# LPEM.net
KiCad netlist of a schematic drawn in EAGLE
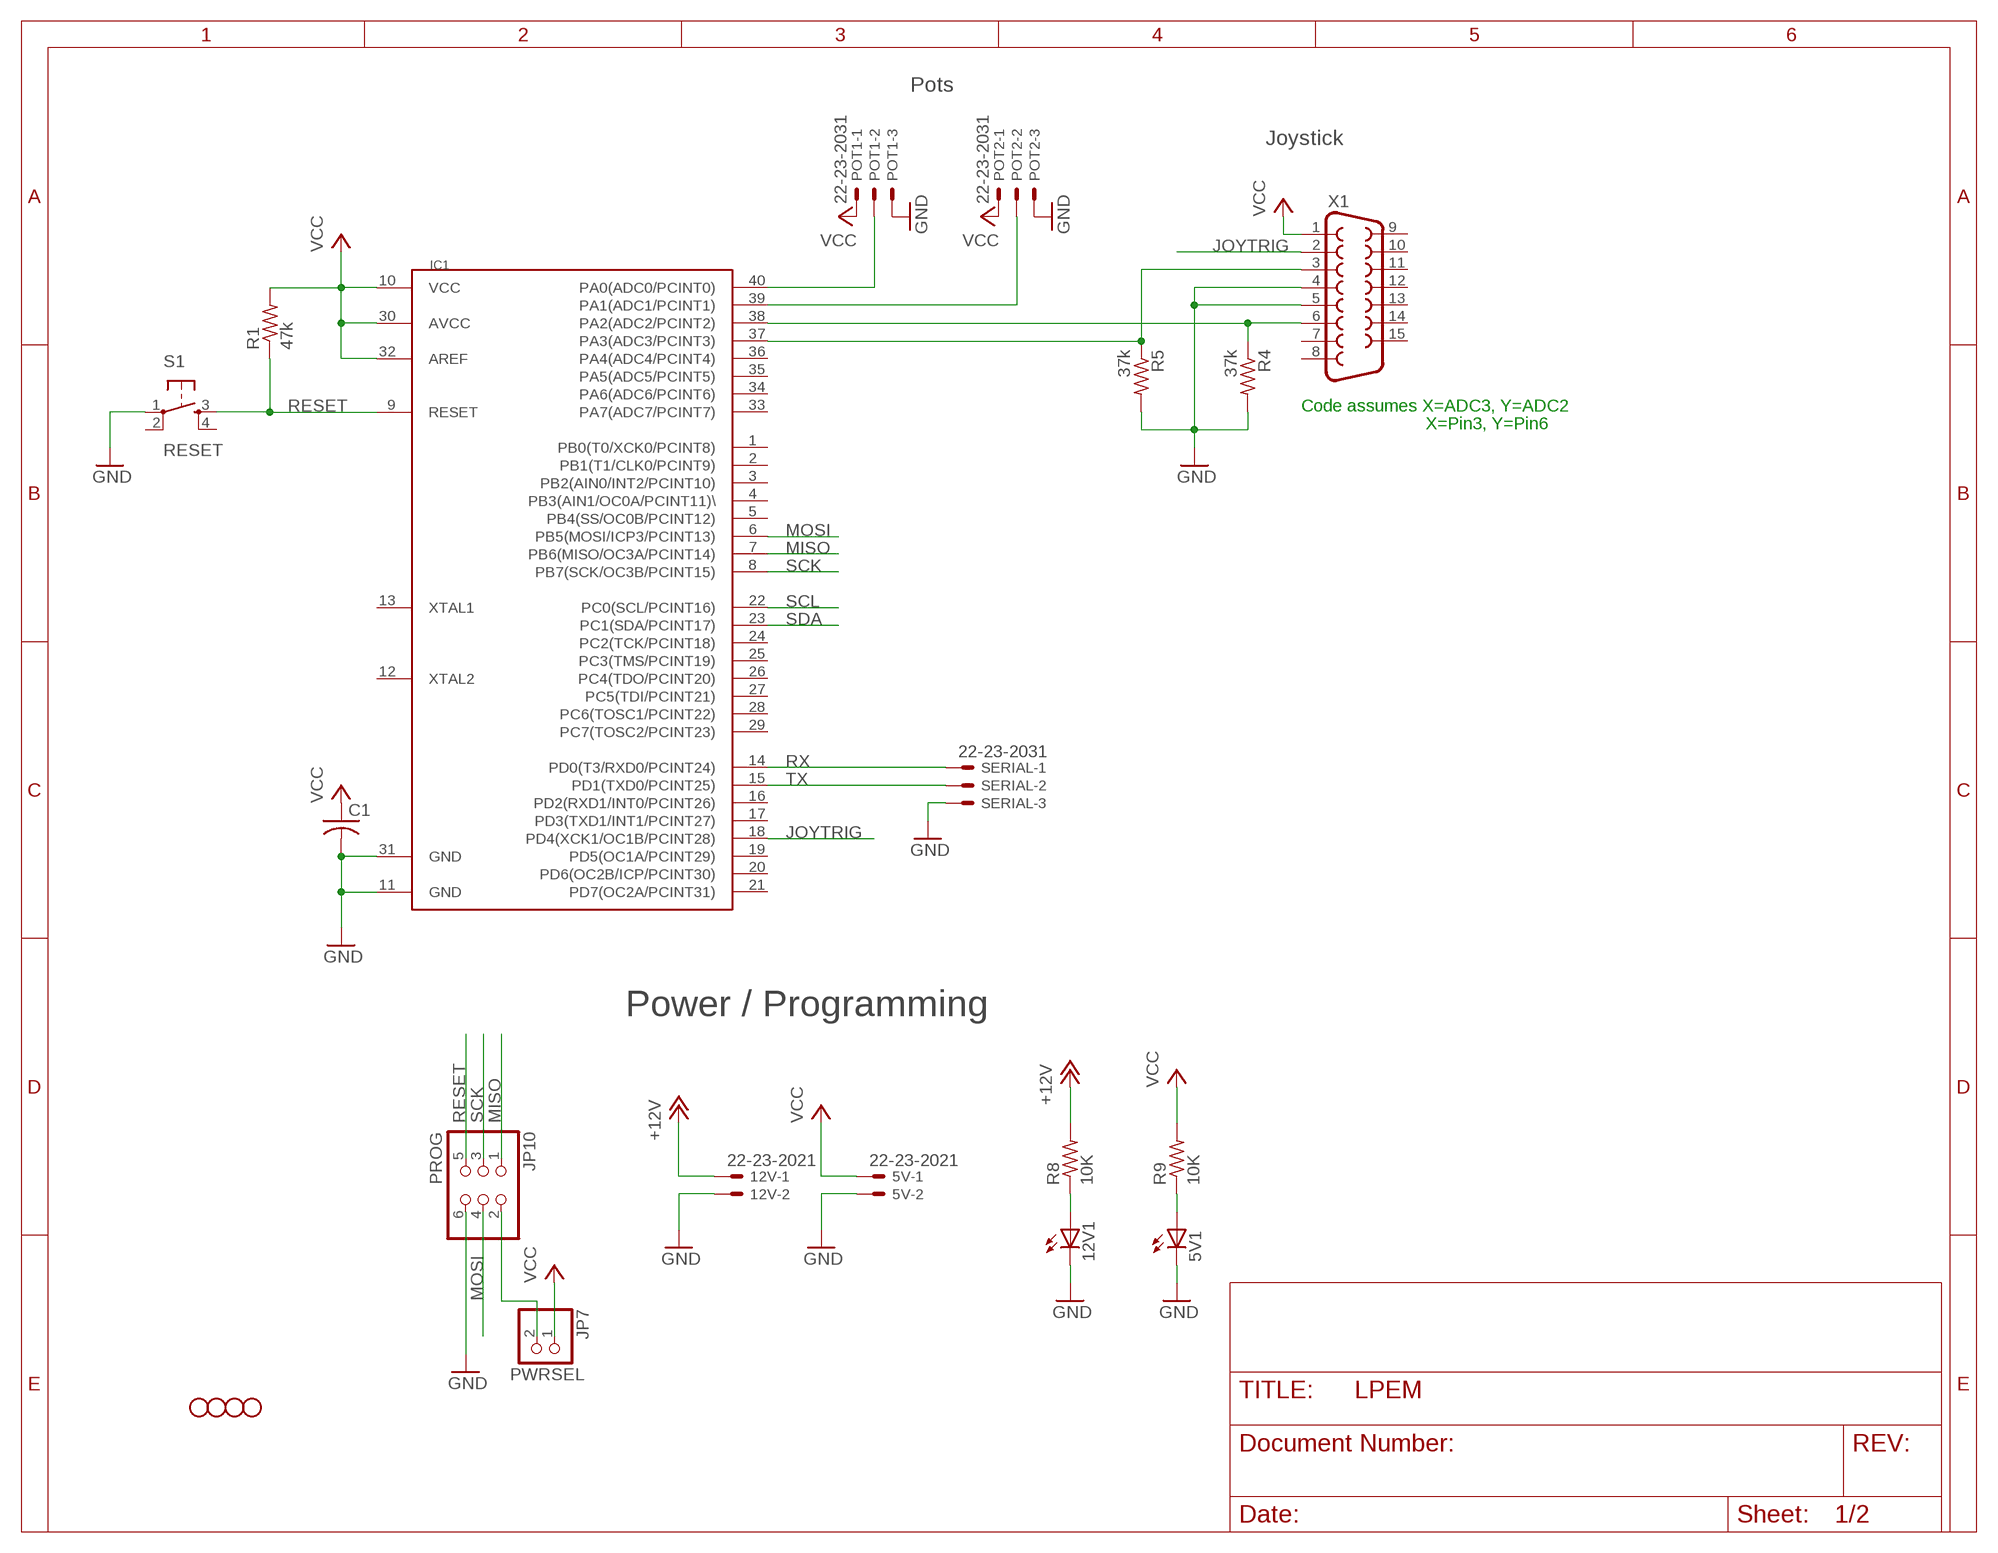
[diagram p0: schematic, sheet 1]
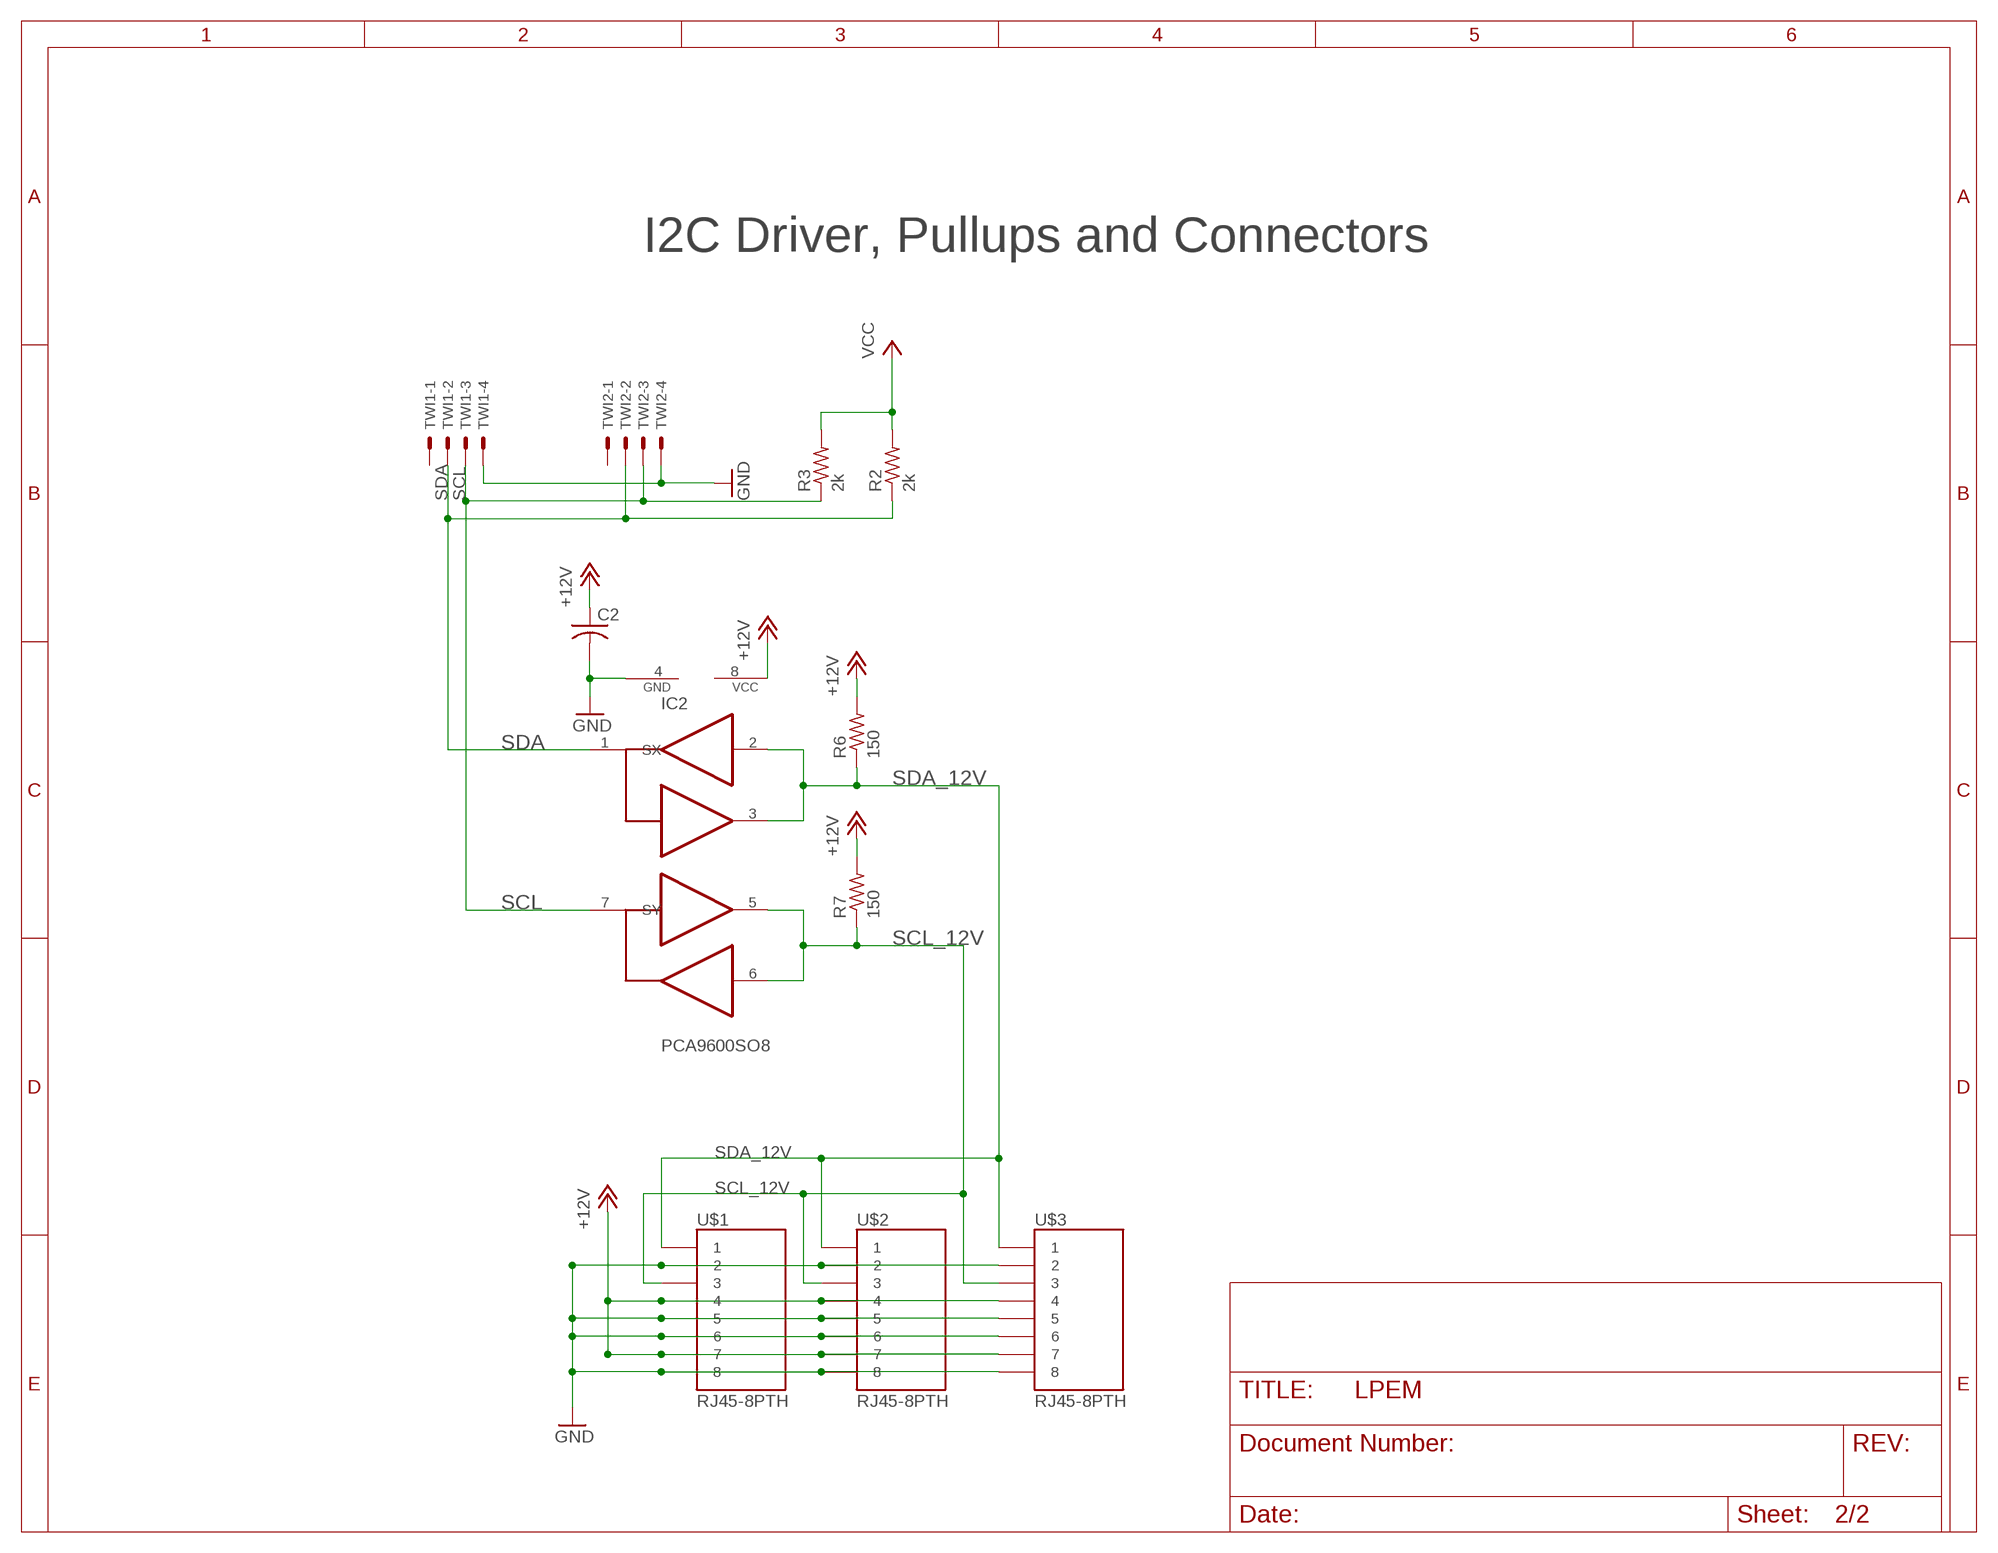
[diagram p1: schematic, sheet 2]

(export (version "E")
  (design (tool "Eeschema 10.0.6"))
  (components
    (comp (ref "5V")
      (value "22-23-2021")
      (footprint "eagle-import:22-23-2021")
      (libsource (lib "eagle-import") (part "22-23-2021"))
    )
    (comp (ref "5V1")
      (value "LED3MM")
      (footprint "eagle-import:LED3MM")
      (libsource (lib "eagle-import") (part "LED3MM"))
    )
    (comp (ref "12V")
      (value "22-23-2021")
      (footprint "eagle-import:22-23-2021")
      (libsource (lib "eagle-import") (part "22-23-2021"))
    )
    (comp (ref "12V1")
      (value "LED3MM")
      (footprint "eagle-import:LED3MM")
      (libsource (lib "eagle-import") (part "LED3MM"))
    )
    (comp (ref "C1")
      (value "C-US025-025X050")
      (footprint "eagle-import:C025-025X050")
      (libsource (lib "eagle-import") (part "C-US025-025X050"))
    )
    (comp (ref "IC1")
      (value "MEGA1284P")
      (footprint "eagle-import:DIL40")
      (libsource (lib "eagle-import") (part "MEGA1284P"))
    )
    (comp (ref "JP1")
      (value "STAND-OFF")
      (footprint "eagle-import:STAND-OFF")
      (libsource (lib "eagle-import") (part "STAND-OFF"))
    )
    (comp (ref "JP2")
      (value "STAND-OFF")
      (footprint "eagle-import:STAND-OFF")
      (libsource (lib "eagle-import") (part "STAND-OFF"))
    )
    (comp (ref "JP7")
      (value "PWRSEL")
      (footprint "eagle-import:1X02")
      (libsource (lib "eagle-import") (part "PINHD-1X2"))
    )
    (comp (ref "JP8")
      (value "STAND-OFF")
      (footprint "eagle-import:STAND-OFF")
      (libsource (lib "eagle-import") (part "STAND-OFF"))
    )
    (comp (ref "JP9")
      (value "STAND-OFF")
      (footprint "eagle-import:STAND-OFF")
      (libsource (lib "eagle-import") (part "STAND-OFF"))
    )
    (comp (ref "JP10")
      (value "PROG")
      (footprint "eagle-import:2X03")
      (libsource (lib "eagle-import") (part "PINHD-2X3"))
    )
    (comp (ref "POT1")
      (value "22-23-2031")
      (footprint "eagle-import:22-23-2031")
      (libsource (lib "eagle-import") (part "22-23-2031"))
    )
    (comp (ref "POT2")
      (value "22-23-2031")
      (footprint "eagle-import:22-23-2031")
      (libsource (lib "eagle-import") (part "22-23-2031"))
    )
    (comp (ref "R1")
      (value "47k")
      (footprint "eagle-import:0204_5")
      (libsource (lib "eagle-import") (part "R-US_0204/5"))
    )
    (comp (ref "R4")
      (value "37k")
      (footprint "eagle-import:0204_5")
      (libsource (lib "eagle-import") (part "R-US_0204/5"))
    )
    (comp (ref "R5")
      (value "37k")
      (footprint "eagle-import:0204_5")
      (libsource (lib "eagle-import") (part "R-US_0204/5"))
    )
    (comp (ref "R8")
      (value "10K")
      (footprint "eagle-import:0204_5")
      (libsource (lib "eagle-import") (part "R-US_0204/5"))
    )
    (comp (ref "R9")
      (value "10K")
      (footprint "eagle-import:0204_5")
      (libsource (lib "eagle-import") (part "R-US_0204/5"))
    )
    (comp (ref "S1")
      (value "RESET")
      (footprint "eagle-import:TACTILE-PTH")
      (libsource (lib "eagle-import") (part "TAC_SWITCHPTH"))
    )
    (comp (ref "SERIAL")
      (value "22-23-2031")
      (footprint "eagle-import:22-23-2031")
      (libsource (lib "eagle-import") (part "22-23-2031"))
    )
    (comp (ref "X1")
      (value "F15HP")
      (footprint "eagle-import:F15HP")
      (libsource (lib "eagle-import") (part "F15HP"))
    )
    (comp (ref "C2")
      (value "C-US025-025X050")
      (footprint "eagle-import:C025-025X050")
      (libsource (lib "eagle-import") (part "C-US025-025X050"))
    )
    (comp (ref "IC2")
      (value "PCA9600SO8")
      (footprint "eagle-import:SO08")
      (libsource (lib "eagle-import") (part "PCA9600SO8"))
    )
    (comp (ref "R2")
      (value "2k")
      (footprint "eagle-import:0204_5")
      (libsource (lib "eagle-import") (part "R-US_0204/5"))
    )
    (comp (ref "R3")
      (value "2k")
      (footprint "eagle-import:0204_5")
      (libsource (lib "eagle-import") (part "R-US_0204/5"))
    )
    (comp (ref "R6")
      (value "150")
      (footprint "eagle-import:0204_5")
      (libsource (lib "eagle-import") (part "R-US_0204/5"))
    )
    (comp (ref "R7")
      (value "150")
      (footprint "eagle-import:0204_5")
      (libsource (lib "eagle-import") (part "R-US_0204/5"))
    )
    (comp (ref "TWI1")
      (value "22-23-2041")
      (footprint "eagle-import:22-23-2041")
      (libsource (lib "eagle-import") (part "22-23-2041"))
    )
    (comp (ref "TWI2")
      (value "22-23-2041")
      (footprint "eagle-import:22-23-2041")
      (libsource (lib "eagle-import") (part "22-23-2041"))
    )
    (comp (ref "U$1")
      (value "RJ45-8PTH")
      (footprint "eagle-import:RJ45-8")
      (libsource (lib "eagle-import") (part "RJ45-8PTH"))
    )
    (comp (ref "U$2")
      (value "RJ45-8PTH")
      (footprint "eagle-import:RJ45-8")
      (libsource (lib "eagle-import") (part "RJ45-8PTH"))
    )
    (comp (ref "U$3")
      (value "RJ45-8PTH")
      (footprint "eagle-import:RJ45-8")
      (libsource (lib "eagle-import") (part "RJ45-8PTH"))
    )
  )
  (nets
    (net (code "1") (name "+12V") (class "Default")
      (node (ref "12V") (pin "1") (pinfunction "S_1") (pintype "passive"))
      (node (ref "C2") (pin "1") (pinfunction "1_1") (pintype "passive"))
      (node (ref "IC2") (pin "8") (pinfunction "VCC_8") (pintype "power_in"))
      (node (ref "R6") (pin "2") (pinfunction "2_2") (pintype "passive"))
      (node (ref "R7") (pin "2") (pinfunction "2_2") (pintype "passive"))
      (node (ref "R8") (pin "2") (pinfunction "2_2") (pintype "passive"))
      (node (ref "U$1") (pin "4") (pinfunction "4_4") (pintype "bidirectional"))
      (node (ref "U$1") (pin "7") (pinfunction "7_7") (pintype "bidirectional"))
      (node (ref "U$2") (pin "4") (pinfunction "4_4") (pintype "bidirectional"))
      (node (ref "U$2") (pin "7") (pinfunction "7_7") (pintype "bidirectional"))
      (node (ref "U$3") (pin "4") (pinfunction "4_4") (pintype "bidirectional"))
      (node (ref "U$3") (pin "7") (pinfunction "7_7") (pintype "bidirectional"))
    )
    (net (code "2") (name "GND") (class "Default")
      (node (ref "12V") (pin "2") (pinfunction "S_2") (pintype "passive"))
      (node (ref "12V1") (pin "K") (pinfunction "C_K") (pintype "passive"))
      (node (ref "5V") (pin "2") (pinfunction "S_2") (pintype "passive"))
      (node (ref "5V1") (pin "K") (pinfunction "C_K") (pintype "passive"))
      (node (ref "C1") (pin "2") (pinfunction "2_2") (pintype "passive"))
      (node (ref "C2") (pin "2") (pinfunction "2_2") (pintype "passive"))
      (node (ref "IC1") (pin "11") (pinfunction "GND_11") (pintype "bidirectional"))
      (node (ref "IC1") (pin "31") (pinfunction "GND_31") (pintype "bidirectional"))
      (node (ref "IC2") (pin "4") (pinfunction "GND_4") (pintype "power_in"))
      (node (ref "JP10") (pin "6") (pinfunction "6_6") (pintype "passive"))
      (node (ref "POT1") (pin "3") (pinfunction "S_3") (pintype "passive"))
      (node (ref "POT2") (pin "3") (pinfunction "S_3") (pintype "passive"))
      (node (ref "R4") (pin "2") (pinfunction "2_2") (pintype "passive"))
      (node (ref "R5") (pin "2") (pinfunction "2_2") (pintype "passive"))
      (node (ref "S1") (pin "1") (pinfunction "1_1") (pintype "passive"))
      (node (ref "SERIAL") (pin "3") (pinfunction "S_3") (pintype "passive"))
      (node (ref "TWI1") (pin "4") (pinfunction "S_4") (pintype "passive"))
      (node (ref "TWI2") (pin "4") (pinfunction "S_4") (pintype "passive"))
      (node (ref "U$1") (pin "2") (pinfunction "2_2") (pintype "bidirectional"))
      (node (ref "U$1") (pin "5") (pinfunction "5_5") (pintype "bidirectional"))
      (node (ref "U$1") (pin "6") (pinfunction "6_6") (pintype "bidirectional"))
      (node (ref "U$1") (pin "8") (pinfunction "8_8") (pintype "bidirectional"))
      (node (ref "U$2") (pin "2") (pinfunction "2_2") (pintype "bidirectional"))
      (node (ref "U$2") (pin "5") (pinfunction "5_5") (pintype "bidirectional"))
      (node (ref "U$2") (pin "6") (pinfunction "6_6") (pintype "bidirectional"))
      (node (ref "U$2") (pin "8") (pinfunction "8_8") (pintype "bidirectional"))
      (node (ref "U$3") (pin "2") (pinfunction "2_2") (pintype "bidirectional"))
      (node (ref "U$3") (pin "5") (pinfunction "5_5") (pintype "bidirectional"))
      (node (ref "U$3") (pin "6") (pinfunction "6_6") (pintype "bidirectional"))
      (node (ref "U$3") (pin "8") (pinfunction "8_8") (pintype "bidirectional"))
      (node (ref "X1") (pin "4") (pinfunction "4_4") (pintype "passive"))
      (node (ref "X1") (pin "5") (pinfunction "5_5") (pintype "passive"))
    )
    (net (code "3") (name "JOYTRIG") (class "Default")
      (node (ref "IC1") (pin "18") (pinfunction "PD4(XCK1/OC1B/PCINT28)_18") (pintype "bidirectional"))
      (node (ref "X1") (pin "2") (pinfunction "2_2") (pintype "passive"))
    )
    (net (code "4") (name "MISO") (class "Default")
      (node (ref "IC1") (pin "7") (pinfunction "PB6(MISO/OC3A/PCINT14)_7") (pintype "bidirectional"))
      (node (ref "JP10") (pin "1") (pinfunction "1_1") (pintype "passive"))
    )
    (net (code "5") (name "MOSI") (class "Default")
      (node (ref "IC1") (pin "6") (pinfunction "PB5(MOSI/ICP3/PCINT13)_6") (pintype "bidirectional"))
      (node (ref "JP10") (pin "4") (pinfunction "4_4") (pintype "passive"))
    )
    (net (code "6") (name "Net-(5V1-PadA)") (class "Default")
      (node (ref "5V1") (pin "A") (pinfunction "A_A") (pintype "passive"))
      (node (ref "R9") (pin "1") (pinfunction "1_1") (pintype "passive"))
    )
    (net (code "7") (name "Net-(12V1-PadA)") (class "Default")
      (node (ref "12V1") (pin "A") (pinfunction "A_A") (pintype "passive"))
      (node (ref "R8") (pin "1") (pinfunction "1_1") (pintype "passive"))
    )
    (net (code "8") (name "Net-(IC1-PA0(ADC0{slash}PCINT0))") (class "Default")
      (node (ref "IC1") (pin "40") (pinfunction "PA0(ADC0/PCINT0)_40") (pintype "bidirectional"))
      (node (ref "POT1") (pin "2") (pinfunction "S_2") (pintype "passive"))
    )
    (net (code "9") (name "Net-(IC1-PA1(ADC1{slash}PCINT1))") (class "Default")
      (node (ref "IC1") (pin "39") (pinfunction "PA1(ADC1/PCINT1)_39") (pintype "bidirectional"))
      (node (ref "POT2") (pin "2") (pinfunction "S_2") (pintype "passive"))
    )
    (net (code "10") (name "Net-(IC1-PA2(ADC2{slash}PCINT2))") (class "Default")
      (node (ref "IC1") (pin "38") (pinfunction "PA2(ADC2/PCINT2)_38") (pintype "bidirectional"))
      (node (ref "R4") (pin "1") (pinfunction "1_1") (pintype "passive"))
      (node (ref "X1") (pin "6") (pinfunction "6_6") (pintype "passive"))
    )
    (net (code "11") (name "Net-(IC1-PA3(ADC3{slash}PCINT3))") (class "Default")
      (node (ref "IC1") (pin "37") (pinfunction "PA3(ADC3/PCINT3)_37") (pintype "bidirectional"))
      (node (ref "R5") (pin "1") (pinfunction "1_1") (pintype "passive"))
      (node (ref "X1") (pin "3") (pinfunction "3_3") (pintype "passive"))
    )
    (net (code "12") (name "Net-(JP10-Pad2)") (class "Default")
      (node (ref "JP10") (pin "2") (pinfunction "2_2") (pintype "passive"))
      (node (ref "JP7") (pin "2") (pinfunction "2_2") (pintype "passive"))
    )
    (net (code "13") (name "RESET") (class "Default")
      (node (ref "IC1") (pin "9") (pinfunction "RESET_9") (pintype "bidirectional"))
      (node (ref "JP10") (pin "5") (pinfunction "5_5") (pintype "passive"))
      (node (ref "R1") (pin "1") (pinfunction "1_1") (pintype "passive"))
      (node (ref "S1") (pin "3") (pinfunction "3_3") (pintype "passive"))
    )
    (net (code "14") (name "RX") (class "Default")
      (node (ref "IC1") (pin "14") (pinfunction "PD0(T3/RXD0/PCINT24)_14") (pintype "bidirectional"))
      (node (ref "SERIAL") (pin "1") (pinfunction "S_1") (pintype "passive"))
    )
    (net (code "15") (name "SCK") (class "Default")
      (node (ref "IC1") (pin "8") (pinfunction "PB7(SCK/OC3B/PCINT15)_8") (pintype "bidirectional"))
      (node (ref "JP10") (pin "3") (pinfunction "3_3") (pintype "passive"))
    )
    (net (code "16") (name "SCL") (class "Default")
      (node (ref "IC1") (pin "22") (pinfunction "PC0(SCL/PCINT16)_22") (pintype "bidirectional"))
      (node (ref "IC2") (pin "7") (pinfunction "SY_7") (pintype "bidirectional"))
      (node (ref "R3") (pin "1") (pinfunction "1_1") (pintype "passive"))
      (node (ref "TWI1") (pin "3") (pinfunction "S_3") (pintype "passive"))
      (node (ref "TWI2") (pin "3") (pinfunction "S_3") (pintype "passive"))
    )
    (net (code "17") (name "SCL_12V") (class "Default")
      (node (ref "IC2") (pin "5") (pinfunction "TY_5") (pintype "output"))
      (node (ref "IC2") (pin "6") (pinfunction "RY_6") (pintype "input"))
      (node (ref "R7") (pin "1") (pinfunction "1_1") (pintype "passive"))
      (node (ref "U$1") (pin "3") (pinfunction "3_3") (pintype "bidirectional"))
      (node (ref "U$2") (pin "3") (pinfunction "3_3") (pintype "bidirectional"))
      (node (ref "U$3") (pin "3") (pinfunction "3_3") (pintype "bidirectional"))
    )
    (net (code "18") (name "SDA") (class "Default")
      (node (ref "IC1") (pin "23") (pinfunction "PC1(SDA/PCINT17)_23") (pintype "bidirectional"))
      (node (ref "IC2") (pin "1") (pinfunction "SX_1") (pintype "bidirectional"))
      (node (ref "R2") (pin "1") (pinfunction "1_1") (pintype "passive"))
      (node (ref "TWI1") (pin "2") (pinfunction "S_2") (pintype "passive"))
      (node (ref "TWI2") (pin "2") (pinfunction "S_2") (pintype "passive"))
    )
    (net (code "19") (name "SDA_12V") (class "Default")
      (node (ref "IC2") (pin "2") (pinfunction "RX_2") (pintype "input"))
      (node (ref "IC2") (pin "3") (pinfunction "TX_3") (pintype "output"))
      (node (ref "R6") (pin "1") (pinfunction "1_1") (pintype "passive"))
      (node (ref "U$1") (pin "1") (pinfunction "1_1") (pintype "bidirectional"))
      (node (ref "U$2") (pin "1") (pinfunction "1_1") (pintype "bidirectional"))
      (node (ref "U$3") (pin "1") (pinfunction "1_1") (pintype "bidirectional"))
    )
    (net (code "20") (name "TX") (class "Default")
      (node (ref "IC1") (pin "15") (pinfunction "PD1(TXD0/PCINT25)_15") (pintype "bidirectional"))
      (node (ref "SERIAL") (pin "2") (pinfunction "S_2") (pintype "passive"))
    )
    (net (code "21") (name "VCC") (class "Default")
      (node (ref "5V") (pin "1") (pinfunction "S_1") (pintype "passive"))
      (node (ref "C1") (pin "1") (pinfunction "1_1") (pintype "passive"))
      (node (ref "IC1") (pin "10") (pinfunction "VCC_10") (pintype "bidirectional"))
      (node (ref "IC1") (pin "30") (pinfunction "AVCC_30") (pintype "bidirectional"))
      (node (ref "IC1") (pin "32") (pinfunction "AREF_32") (pintype "bidirectional"))
      (node (ref "JP7") (pin "1") (pinfunction "1_1") (pintype "passive"))
      (node (ref "POT1") (pin "1") (pinfunction "S_1") (pintype "passive"))
      (node (ref "POT2") (pin "1") (pinfunction "S_1") (pintype "passive"))
      (node (ref "R1") (pin "2") (pinfunction "2_2") (pintype "passive"))
      (node (ref "R2") (pin "2") (pinfunction "2_2") (pintype "passive"))
      (node (ref "R3") (pin "2") (pinfunction "2_2") (pintype "passive"))
      (node (ref "R9") (pin "2") (pinfunction "2_2") (pintype "passive"))
      (node (ref "X1") (pin "1") (pinfunction "1_1") (pintype "passive"))
    )
    (net (code "22") (name "unconnected-(IC1-PA4(ADC4{slash}PCINT4)-Pad36)") (class "Default")
      (node (ref "IC1") (pin "36") (pinfunction "PA4(ADC4/PCINT4)_36") (pintype "bidirectional"))
    )
    (net (code "23") (name "unconnected-(IC1-PA5(ADC5{slash}PCINT5)-Pad35)") (class "Default")
      (node (ref "IC1") (pin "35") (pinfunction "PA5(ADC5/PCINT5)_35") (pintype "bidirectional"))
    )
    (net (code "24") (name "unconnected-(IC1-PA6(ADC6{slash}PCINT6)-Pad34)") (class "Default")
      (node (ref "IC1") (pin "34") (pinfunction "PA6(ADC6/PCINT6)_34") (pintype "bidirectional"))
    )
    (net (code "25") (name "unconnected-(IC1-PA7(ADC7{slash}PCINT7)-Pad33)") (class "Default")
      (node (ref "IC1") (pin "33") (pinfunction "PA7(ADC7/PCINT7)_33") (pintype "bidirectional"))
    )
    (net (code "26") (name "unconnected-(IC1-PB0(T0{slash}XCK0{slash}PCINT8)-Pad1)") (class "Default")
      (node (ref "IC1") (pin "1") (pinfunction "PB0(T0/XCK0/PCINT8)_1") (pintype "bidirectional"))
    )
    (net (code "27") (name "unconnected-(IC1-PB1(T1{slash}CLK0{slash}PCINT9)-Pad2)") (class "Default")
      (node (ref "IC1") (pin "2") (pinfunction "PB1(T1/CLK0/PCINT9)_2") (pintype "bidirectional"))
    )
    (net (code "28") (name "unconnected-(IC1-PB2(AIN0{slash}INT2{slash}PCINT10)-Pad3)") (class "Default")
      (node (ref "IC1") (pin "3") (pinfunction "PB2(AIN0/INT2/PCINT10)_3") (pintype "bidirectional"))
    )
    (net (code "29") (name "unconnected-(IC1-PB3(AIN1{slash}OC0A{slash}PCINT11)\\-Pad4)") (class "Default")
      (node (ref "IC1") (pin "4") (pinfunction "PB3(AIN1/OC0A/PCINT11)\\_4") (pintype "bidirectional"))
    )
    (net (code "30") (name "unconnected-(IC1-PB4(SS{slash}OC0B{slash}PCINT12)-Pad5)") (class "Default")
      (node (ref "IC1") (pin "5") (pinfunction "PB4(SS/OC0B/PCINT12)_5") (pintype "bidirectional"))
    )
    (net (code "31") (name "unconnected-(IC1-PC2(TCK{slash}PCINT18)-Pad24)") (class "Default")
      (node (ref "IC1") (pin "24") (pinfunction "PC2(TCK/PCINT18)_24") (pintype "bidirectional"))
    )
    (net (code "32") (name "unconnected-(IC1-PC3(TMS{slash}PCINT19)-Pad25)") (class "Default")
      (node (ref "IC1") (pin "25") (pinfunction "PC3(TMS/PCINT19)_25") (pintype "bidirectional"))
    )
    (net (code "33") (name "unconnected-(IC1-PC4(TDO{slash}PCINT20)-Pad26)") (class "Default")
      (node (ref "IC1") (pin "26") (pinfunction "PC4(TDO/PCINT20)_26") (pintype "bidirectional"))
    )
    (net (code "34") (name "unconnected-(IC1-PC5(TDI{slash}PCINT21)-Pad27)") (class "Default")
      (node (ref "IC1") (pin "27") (pinfunction "PC5(TDI/PCINT21)_27") (pintype "bidirectional"))
    )
    (net (code "35") (name "unconnected-(IC1-PC6(TOSC1{slash}PCINT22)-Pad28)") (class "Default")
      (node (ref "IC1") (pin "28") (pinfunction "PC6(TOSC1/PCINT22)_28") (pintype "bidirectional"))
    )
    (net (code "36") (name "unconnected-(IC1-PC7(TOSC2{slash}PCINT23)-Pad29)") (class "Default")
      (node (ref "IC1") (pin "29") (pinfunction "PC7(TOSC2/PCINT23)_29") (pintype "bidirectional"))
    )
    (net (code "37") (name "unconnected-(IC1-PD2(RXD1{slash}INT0{slash}PCINT26)-Pad16)") (class "Default")
      (node (ref "IC1") (pin "16") (pinfunction "PD2(RXD1/INT0/PCINT26)_16") (pintype "bidirectional"))
    )
    (net (code "38") (name "unconnected-(IC1-PD3(TXD1{slash}INT1{slash}PCINT27)-Pad17)") (class "Default")
      (node (ref "IC1") (pin "17") (pinfunction "PD3(TXD1/INT1/PCINT27)_17") (pintype "bidirectional"))
    )
    (net (code "39") (name "unconnected-(IC1-PD5(OC1A{slash}PCINT29)-Pad19)") (class "Default")
      (node (ref "IC1") (pin "19") (pinfunction "PD5(OC1A/PCINT29)_19") (pintype "bidirectional"))
    )
    (net (code "40") (name "unconnected-(IC1-PD6(OC2B{slash}ICP{slash}PCINT30)-Pad20)") (class "Default")
      (node (ref "IC1") (pin "20") (pinfunction "PD6(OC2B/ICP/PCINT30)_20") (pintype "bidirectional"))
    )
    (net (code "41") (name "unconnected-(IC1-PD7(OC2A{slash}PCINT31)-Pad21)") (class "Default")
      (node (ref "IC1") (pin "21") (pinfunction "PD7(OC2A/PCINT31)_21") (pintype "bidirectional"))
    )
    (net (code "42") (name "unconnected-(IC1-XTAL1-Pad13)") (class "Default")
      (node (ref "IC1") (pin "13") (pinfunction "XTAL1_13") (pintype "bidirectional"))
    )
    (net (code "43") (name "unconnected-(IC1-XTAL2-Pad12)") (class "Default")
      (node (ref "IC1") (pin "12") (pinfunction "XTAL2_12") (pintype "bidirectional"))
    )
    (net (code "44") (name "unconnected-(S1-Pad2)") (class "Default")
      (node (ref "S1") (pin "2") (pinfunction "2_2") (pintype "passive"))
    )
    (net (code "45") (name "unconnected-(S1-Pad4)") (class "Default")
      (node (ref "S1") (pin "4") (pinfunction "4_4") (pintype "passive"))
    )
    (net (code "46") (name "unconnected-(TWI1A-S-Pad1)") (class "Default")
      (node (ref "TWI1") (pin "1") (pinfunction "S_1") (pintype "passive"))
    )
    (net (code "47") (name "unconnected-(TWI2A-S-Pad1)") (class "Default")
      (node (ref "TWI2") (pin "1") (pinfunction "S_1") (pintype "passive"))
    )
    (net (code "48") (name "unconnected-(X1-Pad7)") (class "Default")
      (node (ref "X1") (pin "7") (pinfunction "7_7") (pintype "passive"))
    )
    (net (code "49") (name "unconnected-(X1-Pad8)") (class "Default")
      (node (ref "X1") (pin "8") (pinfunction "8_8") (pintype "passive"))
    )
    (net (code "50") (name "unconnected-(X1-Pad9)") (class "Default")
      (node (ref "X1") (pin "9") (pinfunction "9_9") (pintype "passive"))
    )
    (net (code "51") (name "unconnected-(X1-Pad10)") (class "Default")
      (node (ref "X1") (pin "10") (pinfunction "10_10") (pintype "passive"))
    )
    (net (code "52") (name "unconnected-(X1-Pad11)") (class "Default")
      (node (ref "X1") (pin "11") (pinfunction "11_11") (pintype "passive"))
    )
    (net (code "53") (name "unconnected-(X1-Pad12)") (class "Default")
      (node (ref "X1") (pin "12") (pinfunction "12_12") (pintype "passive"))
    )
    (net (code "54") (name "unconnected-(X1-Pad13)") (class "Default")
      (node (ref "X1") (pin "13") (pinfunction "13_13") (pintype "passive"))
    )
    (net (code "55") (name "unconnected-(X1-Pad14)") (class "Default")
      (node (ref "X1") (pin "14") (pinfunction "14_14") (pintype "passive"))
    )
    (net (code "56") (name "unconnected-(X1-Pad15)") (class "Default")
      (node (ref "X1") (pin "15") (pinfunction "15_15") (pintype "passive"))
    )
  )
)
